# Interface.net
KiCad netlist of a schematic drawn in Altium Designer
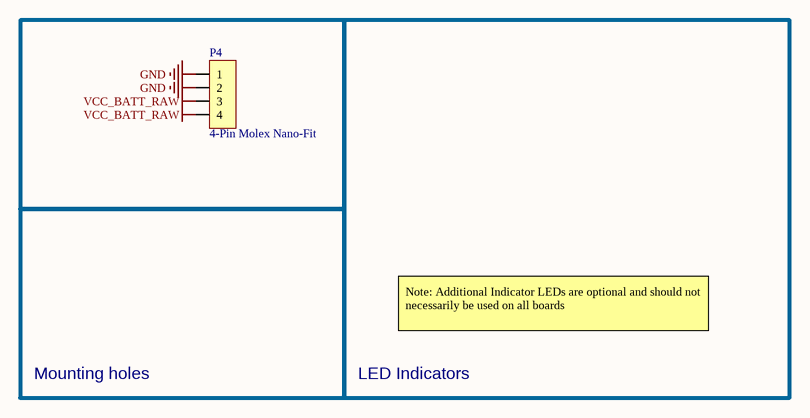
[diagram p0: Interface.SchDoc]

(export (version "E")
  (design (tool "Eeschema 10.0.6"))
  (components
    (comp (ref "P4")
      (value "4-Pin Molex Nano-Fit")
      (footprint "MOLEX NANO-FIT 1X4")
      (description "NanoFit RA Hdr TH SR 4Ckt")
      (fields (field (name "MANUFACTURER") "Molex") (field (name "PART NUMBER") "105313-1204"))
      (libsource (lib "CMR_Connectors") (part "4-Pin Nano-Fit"))
    )
  )
  (nets
    (net (code "1") (name "GND") (class "Default")
      (node (ref "P4") (pin "1") (pinfunction "1_1") (pintype "passive"))
      (node (ref "P4") (pin "2") (pinfunction "2_2") (pintype "passive"))
    )
    (net (code "2") (name "VCC_BATT_RAW") (class "Default")
      (node (ref "P4") (pin "3") (pinfunction "3_3") (pintype "passive"))
      (node (ref "P4") (pin "4") (pinfunction "4_4") (pintype "passive"))
    )
  )
)
